# fpga_radio.net
KiCad netlist of a schematic drawn in Altium Designer
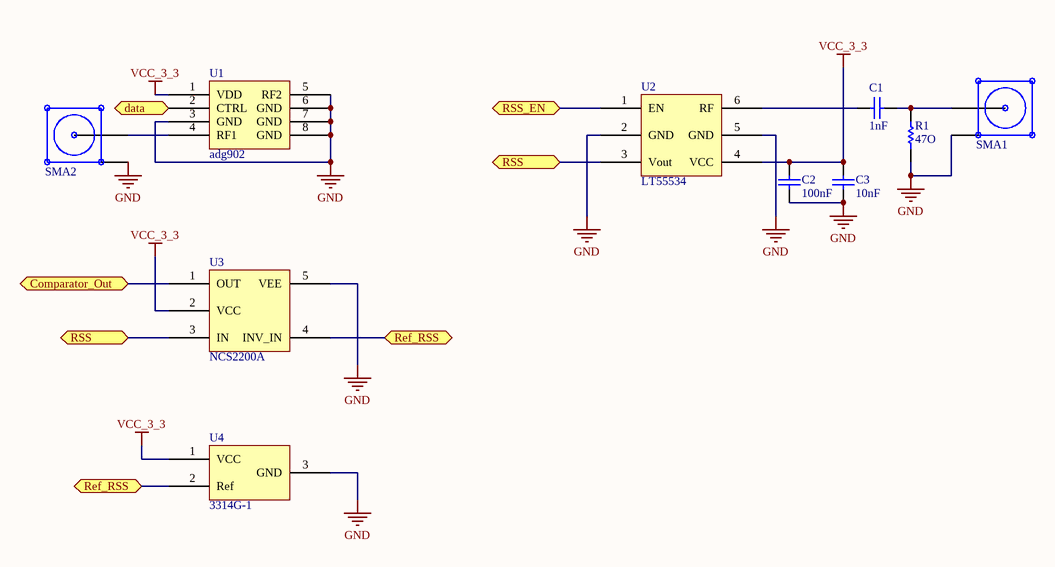
[diagram p0: fpga_radio.SchDoc]

(export (version "E")
  (design (tool "Eeschema 10.0.6"))
  (components
    (comp (ref "C1")
      (value "1nF")
      (footprint "0603")
      (description "Ceramic Capacitor (Surface Mount)")
      (fields (field (name "MANUFACTURER") "Generic Ceramic Chip Cap (TBD)") (field (name "Comment") "Cap"))
      (libsource (lib "wisp") (part "Cap"))
    )
    (comp (ref "C2")
      (value "100nF")
      (footprint "0603")
      (description "Ceramic Capacitor (Surface Mount)")
      (fields (field (name "MANUFACTURER") "Generic Ceramic Chip Cap (TBD)") (field (name "Comment") "Cap"))
      (libsource (lib "wisp") (part "Cap"))
    )
    (comp (ref "C3")
      (value "10nF")
      (footprint "0603")
      (description "Ceramic Capacitor (Surface Mount)")
      (fields (field (name "MANUFACTURER") "Generic Ceramic Chip Cap (TBD)") (field (name "Comment") "Cap"))
      (libsource (lib "wisp") (part "Cap"))
    )
    (comp (ref "R1")
      (value "47O")
      (footprint "0603")
      (description "Chip Resistor (Surface Mount)")
      (fields (field (name "MANUFACTURER") "Generic Chip Res (TBD)") (field (name "Comment") "Res"))
      (libsource (lib "wisp") (part "Res"))
    )
    (comp (ref "SMA1")
      (value "SMA - Hole - 5 Pin")
      (footprint "SMA - Hole - 5 Pin")
      (description "SMA - Through Hole Connector")
      (libsource (lib "wisp") (part "SMA - Hole - 5 Pin"))
    )
    (comp (ref "SMA2")
      (value "SMA - Hole - 5 Pin")
      (footprint "SMA - Hole - 5 Pin")
      (description "SMA - Through Hole Connector")
      (libsource (lib "wisp") (part "SMA - Hole - 5 Pin"))
    )
    (comp (ref "U1") (value "adg902") (footprint "ADG902") (libsource (lib "pengyulib") (part "adg902")))
    (comp (ref "U2") (value "LT55534") (footprint "LT5534") (libsource (lib "pengyulib") (part "LT55534")))
    (comp (ref "U3") (value "NCS2200A") (footprint "NCS2200") (libsource (lib "pengyulib") (part "NCS2200A")))
    (comp (ref "U4") (value "3314G-1") (footprint "3314G-1") (libsource (lib "pengyulib") (part "3314G-1")))
  )
  (nets
    (net (code "1") (name "/Comparator_Out") (class "Default")
      (node (ref "U3") (pin "1") (pinfunction "OUT_1") (pintype "passive"))
    )
    (net (code "2") (name "/RSS") (class "Default")
      (node (ref "U2") (pin "3") (pinfunction "Vout_3") (pintype "passive"))
      (node (ref "U3") (pin "3") (pinfunction "IN_3") (pintype "passive"))
    )
    (net (code "3") (name "/RSS_EN") (class "Default")
      (node (ref "U2") (pin "1") (pinfunction "EN_1") (pintype "passive"))
    )
    (net (code "4") (name "/Ref_RSS") (class "Default")
      (node (ref "U3") (pin "4") (pinfunction "INV_IN_4") (pintype "passive"))
      (node (ref "U4") (pin "2") (pinfunction "Ref_2") (pintype "passive"))
    )
    (net (code "5") (name "/data") (class "Default")
      (node (ref "U1") (pin "2") (pinfunction "CTRL_2") (pintype "passive"))
    )
    (net (code "6") (name "GND") (class "Default")
      (node (ref "C2") (pin "1") (pinfunction "1_1") (pintype "passive"))
      (node (ref "C3") (pin "1") (pinfunction "1_1") (pintype "passive"))
      (node (ref "R1") (pin "1") (pinfunction "1_1") (pintype "passive"))
      (node (ref "SMA1") (pin "1") (pinfunction "1_1") (pintype "passive"))
      (node (ref "SMA2") (pin "1") (pinfunction "1_1") (pintype "passive"))
      (node (ref "U1") (pin "3") (pinfunction "GND_3") (pintype "passive"))
      (node (ref "U1") (pin "5") (pinfunction "RF2_5") (pintype "passive"))
      (node (ref "U1") (pin "6") (pinfunction "GND_6") (pintype "passive"))
      (node (ref "U1") (pin "7") (pinfunction "GND_7") (pintype "passive"))
      (node (ref "U1") (pin "8") (pinfunction "GND_8") (pintype "passive"))
      (node (ref "U2") (pin "2") (pinfunction "GND_2") (pintype "passive"))
      (node (ref "U2") (pin "5") (pinfunction "GND_5") (pintype "passive"))
      (node (ref "U3") (pin "5") (pinfunction "VEE_5") (pintype "passive"))
      (node (ref "U4") (pin "3") (pinfunction "GND_3") (pintype "passive"))
    )
    (net (code "7") (name "Net-(C1-Pad2)") (class "Default")
      (node (ref "C1") (pin "2") (pinfunction "2_2") (pintype "passive"))
      (node (ref "R1") (pin "2") (pinfunction "2_2") (pintype "passive"))
      (node (ref "SMA1") (pin "2") (pinfunction "2_2") (pintype "passive"))
    )
    (net (code "8") (name "Net-(U1-RF1)") (class "Default")
      (node (ref "SMA2") (pin "2") (pinfunction "2_2") (pintype "passive"))
      (node (ref "U1") (pin "4") (pinfunction "RF1_4") (pintype "passive"))
    )
    (net (code "9") (name "Net-(U2-RF)") (class "Default")
      (node (ref "C1") (pin "1") (pinfunction "1_1") (pintype "passive"))
      (node (ref "U2") (pin "6") (pinfunction "RF_6") (pintype "passive"))
    )
    (net (code "10") (name "VCC_3_3") (class "Default")
      (node (ref "C2") (pin "2") (pinfunction "2_2") (pintype "passive"))
      (node (ref "C3") (pin "2") (pinfunction "2_2") (pintype "passive"))
      (node (ref "U1") (pin "1") (pinfunction "VDD_1") (pintype "passive"))
      (node (ref "U2") (pin "4") (pinfunction "VCC_4") (pintype "passive"))
      (node (ref "U3") (pin "2") (pinfunction "VCC_2") (pintype "passive"))
      (node (ref "U4") (pin "1") (pinfunction "VCC_1") (pintype "passive"))
    )
  )
)
